# ftdiy.net
KiCad netlist of a schematic drawn in EAGLE
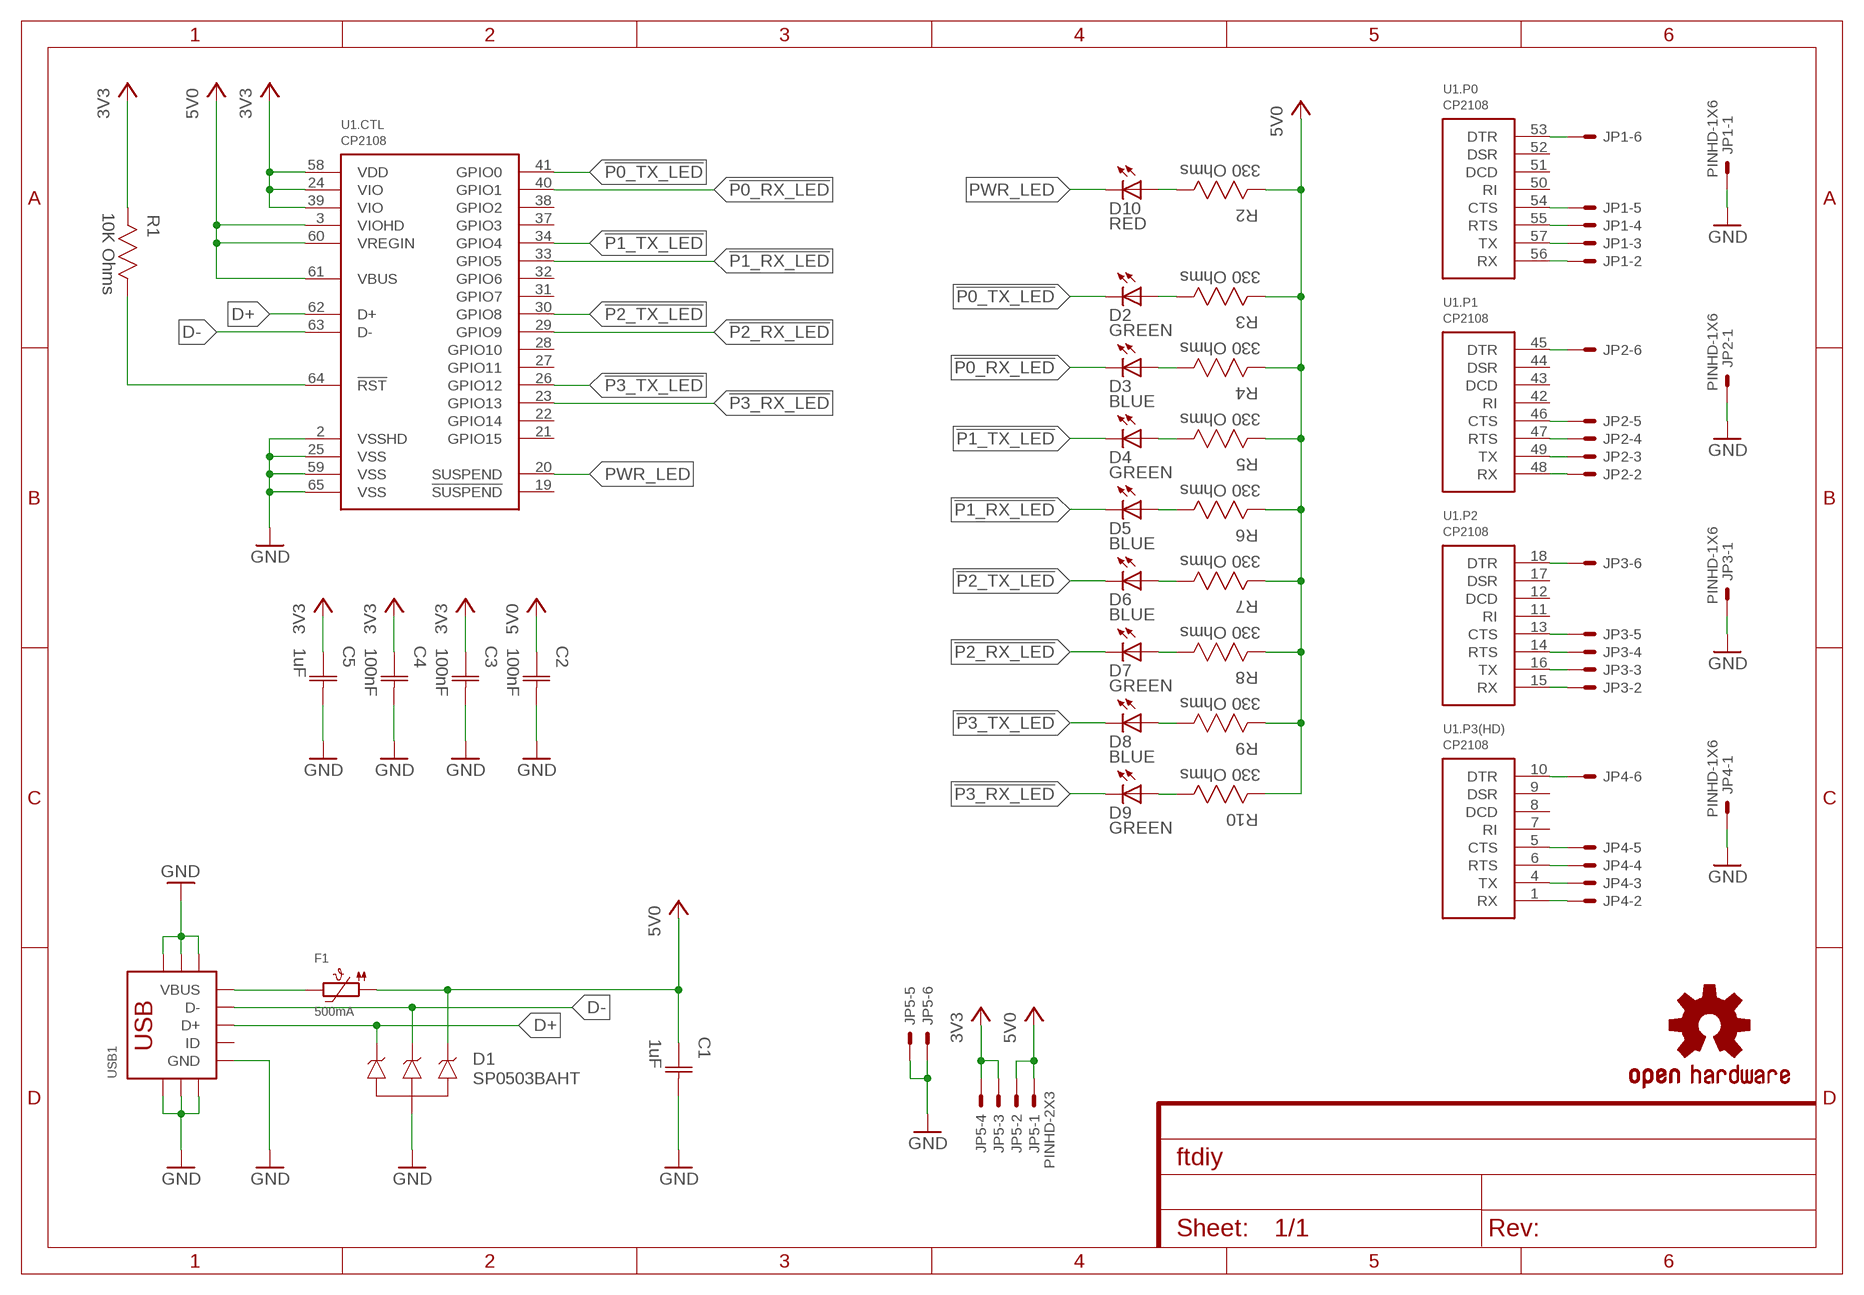
[diagram p0: schematic, sheet 1]

(export (version "E")
  (design (tool "Eeschema 10.0.6"))
  (components
    (comp (ref "C1")
      (value "1uF")
      (footprint "eagle-import:CAP0603")
      (libsource (lib "eagle-import") (part "CAPACITOR-0603"))
    )
    (comp (ref "C2")
      (value "100nF")
      (footprint "eagle-import:CAP0603")
      (libsource (lib "eagle-import") (part "CAPACITOR-0603"))
    )
    (comp (ref "C3")
      (value "100nF")
      (footprint "eagle-import:CAP0603")
      (libsource (lib "eagle-import") (part "CAPACITOR-0603"))
    )
    (comp (ref "C4")
      (value "100nF")
      (footprint "eagle-import:CAP0603")
      (libsource (lib "eagle-import") (part "CAPACITOR-0603"))
    )
    (comp (ref "C5")
      (value "1uF")
      (footprint "eagle-import:CAP0603")
      (libsource (lib "eagle-import") (part "CAPACITOR-0603"))
    )
    (comp (ref "D1")
      (value "SP0503BAHT")
      (footprint "eagle-import:SOT143")
      (libsource (lib "eagle-import") (part "SP0503BAHT"))
    )
    (comp (ref "D2")
      (value "GREEN")
      (footprint "eagle-import:0603")
      (libsource (lib "eagle-import") (part "LED0603"))
    )
    (comp (ref "D3")
      (value "BLUE")
      (footprint "eagle-import:0603")
      (libsource (lib "eagle-import") (part "LED0603"))
    )
    (comp (ref "D4")
      (value "GREEN")
      (footprint "eagle-import:0603")
      (libsource (lib "eagle-import") (part "LED0603"))
    )
    (comp (ref "D5")
      (value "BLUE")
      (footprint "eagle-import:0603")
      (libsource (lib "eagle-import") (part "LED0603"))
    )
    (comp (ref "D6")
      (value "BLUE")
      (footprint "eagle-import:0603")
      (libsource (lib "eagle-import") (part "LED0603"))
    )
    (comp (ref "D7")
      (value "GREEN")
      (footprint "eagle-import:0603")
      (libsource (lib "eagle-import") (part "LED0603"))
    )
    (comp (ref "D8")
      (value "BLUE")
      (footprint "eagle-import:0603")
      (libsource (lib "eagle-import") (part "LED0603"))
    )
    (comp (ref "D9")
      (value "GREEN")
      (footprint "eagle-import:0603")
      (libsource (lib "eagle-import") (part "LED0603"))
    )
    (comp (ref "D10")
      (value "RED")
      (footprint "eagle-import:0603")
      (libsource (lib "eagle-import") (part "LED0603"))
    )
    (comp (ref "F1")
      (value "500mA")
      (footprint "eagle-import:1206")
      (libsource (lib "eagle-import") (part "PTC1206"))
    )
    (comp (ref "JP1")
      (value "PINHD-1X6")
      (footprint "eagle-import:1X06")
      (libsource (lib "eagle-import") (part "PINHD-1X6"))
    )
    (comp (ref "JP2")
      (value "PINHD-1X6")
      (footprint "eagle-import:1X06")
      (libsource (lib "eagle-import") (part "PINHD-1X6"))
    )
    (comp (ref "JP3")
      (value "PINHD-1X6")
      (footprint "eagle-import:1X06")
      (libsource (lib "eagle-import") (part "PINHD-1X6"))
    )
    (comp (ref "JP4")
      (value "PINHD-1X6")
      (footprint "eagle-import:1X06")
      (libsource (lib "eagle-import") (part "PINHD-1X6"))
    )
    (comp (ref "JP5")
      (value "PINHD-2X3")
      (footprint "eagle-import:2X03")
      (libsource (lib "eagle-import") (part "PINHD-2X3"))
    )
    (comp (ref "LOGO1")
      (value "OSHW-LOGOM")
      (footprint "eagle-import:OSHW-LOGO-M")
      (libsource (lib "eagle-import") (part "OSHW-LOGOM"))
    )
    (comp (ref "R1")
      (value "10K Ohms")
      (footprint "eagle-import:RES0603")
      (libsource (lib "eagle-import") (part "RESISTOR-0603"))
    )
    (comp (ref "R2")
      (value "330 Ohms")
      (footprint "eagle-import:RES0603")
      (libsource (lib "eagle-import") (part "RESISTOR-0603"))
    )
    (comp (ref "R3")
      (value "330 Ohms")
      (footprint "eagle-import:RES0603")
      (libsource (lib "eagle-import") (part "RESISTOR-0603"))
    )
    (comp (ref "R4")
      (value "330 Ohms")
      (footprint "eagle-import:RES0603")
      (libsource (lib "eagle-import") (part "RESISTOR-0603"))
    )
    (comp (ref "R5")
      (value "330 Ohms")
      (footprint "eagle-import:RES0603")
      (libsource (lib "eagle-import") (part "RESISTOR-0603"))
    )
    (comp (ref "R6")
      (value "330 Ohms")
      (footprint "eagle-import:RES0603")
      (libsource (lib "eagle-import") (part "RESISTOR-0603"))
    )
    (comp (ref "R7")
      (value "330 Ohms")
      (footprint "eagle-import:RES0603")
      (libsource (lib "eagle-import") (part "RESISTOR-0603"))
    )
    (comp (ref "R8")
      (value "330 Ohms")
      (footprint "eagle-import:RES0603")
      (libsource (lib "eagle-import") (part "RESISTOR-0603"))
    )
    (comp (ref "R9")
      (value "330 Ohms")
      (footprint "eagle-import:RES0603")
      (libsource (lib "eagle-import") (part "RESISTOR-0603"))
    )
    (comp (ref "R10")
      (value "330 Ohms")
      (footprint "eagle-import:RES0603")
      (libsource (lib "eagle-import") (part "RESISTOR-0603"))
    )
    (comp (ref "U1")
      (value "CP2108")
      (footprint "eagle-import:QFN64")
      (libsource (lib "eagle-import") (part "CP2108"))
    )
    (comp (ref "USB1")
      (value "USB-MICRO-B-SMD-FLAT-SIDE")
      (footprint "eagle-import:USB-MICRO-B-SMD-FLAT-SIDE")
      (libsource (lib "eagle-import") (part "USB-MICRO-B-SMD-FLAT-SIDE"))
    )
  )
  (nets
    (net (code "1") (name "/~{P0_RX_LED}") (class "Default")
      (node (ref "D3") (pin "1") (pinfunction "C_1") (pintype "passive"))
      (node (ref "U1") (pin "40") (pinfunction "GPIO1_40") (pintype "bidirectional"))
    )
    (net (code "2") (name "/~{P0_TX_LED}") (class "Default")
      (node (ref "D2") (pin "1") (pinfunction "C_1") (pintype "passive"))
      (node (ref "U1") (pin "41") (pinfunction "GPIO0_41") (pintype "bidirectional"))
    )
    (net (code "3") (name "/~{P1_RX_LED}") (class "Default")
      (node (ref "D5") (pin "1") (pinfunction "C_1") (pintype "passive"))
      (node (ref "U1") (pin "33") (pinfunction "GPIO5_33") (pintype "bidirectional"))
    )
    (net (code "4") (name "/~{P1_TX_LED}") (class "Default")
      (node (ref "D4") (pin "1") (pinfunction "C_1") (pintype "passive"))
      (node (ref "U1") (pin "34") (pinfunction "GPIO4_34") (pintype "bidirectional"))
    )
    (net (code "5") (name "/~{P2_RX_LED}") (class "Default")
      (node (ref "D7") (pin "1") (pinfunction "C_1") (pintype "passive"))
      (node (ref "U1") (pin "29") (pinfunction "GPIO9_29") (pintype "bidirectional"))
    )
    (net (code "6") (name "/~{P2_TX_LED}") (class "Default")
      (node (ref "D6") (pin "1") (pinfunction "C_1") (pintype "passive"))
      (node (ref "U1") (pin "30") (pinfunction "GPIO8_30") (pintype "bidirectional"))
    )
    (net (code "7") (name "/~{P3_RX_LED}") (class "Default")
      (node (ref "D9") (pin "1") (pinfunction "C_1") (pintype "passive"))
      (node (ref "U1") (pin "23") (pinfunction "GPIO13_23") (pintype "bidirectional"))
    )
    (net (code "8") (name "/~{P3_TX_LED}") (class "Default")
      (node (ref "D8") (pin "1") (pinfunction "C_1") (pintype "passive"))
      (node (ref "U1") (pin "26") (pinfunction "GPIO12_26") (pintype "bidirectional"))
    )
    (net (code "9") (name "3V3") (class "Default")
      (node (ref "C3") (pin "1") (pinfunction "C1_1") (pintype "passive"))
      (node (ref "C4") (pin "1") (pinfunction "C1_1") (pintype "passive"))
      (node (ref "C5") (pin "1") (pinfunction "C1_1") (pintype "passive"))
      (node (ref "JP5") (pin "3") (pinfunction "S_3") (pintype "passive"))
      (node (ref "JP5") (pin "4") (pinfunction "S_4") (pintype "passive"))
      (node (ref "R1") (pin "2") (pinfunction "2_2") (pintype "passive"))
      (node (ref "U1") (pin "24") (pinfunction "VIO_24") (pintype "bidirectional"))
      (node (ref "U1") (pin "39") (pinfunction "VIO_39") (pintype "bidirectional"))
      (node (ref "U1") (pin "58") (pinfunction "VDD_58") (pintype "bidirectional"))
    )
    (net (code "10") (name "5V0") (class "Default")
      (node (ref "C1") (pin "1") (pinfunction "C1_1") (pintype "passive"))
      (node (ref "C2") (pin "1") (pinfunction "C1_1") (pintype "passive"))
      (node (ref "D1") (pin "4") (pinfunction "4_4") (pintype "bidirectional"))
      (node (ref "F1") (pin "1") (pinfunction "1_1") (pintype "passive"))
      (node (ref "JP5") (pin "1") (pinfunction "S_1") (pintype "passive"))
      (node (ref "JP5") (pin "2") (pinfunction "S_2") (pintype "passive"))
      (node (ref "R10") (pin "2") (pinfunction "2_2") (pintype "passive"))
      (node (ref "R2") (pin "2") (pinfunction "2_2") (pintype "passive"))
      (node (ref "R3") (pin "2") (pinfunction "2_2") (pintype "passive"))
      (node (ref "R4") (pin "2") (pinfunction "2_2") (pintype "passive"))
      (node (ref "R5") (pin "2") (pinfunction "2_2") (pintype "passive"))
      (node (ref "R6") (pin "2") (pinfunction "2_2") (pintype "passive"))
      (node (ref "R7") (pin "2") (pinfunction "2_2") (pintype "passive"))
      (node (ref "R8") (pin "2") (pinfunction "2_2") (pintype "passive"))
      (node (ref "R9") (pin "2") (pinfunction "2_2") (pintype "passive"))
      (node (ref "U1") (pin "3") (pinfunction "VIOHD_3") (pintype "bidirectional"))
      (node (ref "U1") (pin "60") (pinfunction "VREGIN_60") (pintype "bidirectional"))
      (node (ref "U1") (pin "61") (pinfunction "VBUS_61") (pintype "bidirectional"))
    )
    (net (code "11") (name "D+") (class "Default")
      (node (ref "D1") (pin "2") (pinfunction "2_2") (pintype "bidirectional"))
      (node (ref "U1") (pin "62") (pinfunction "D+_62") (pintype "bidirectional"))
      (node (ref "USB1") (pin "D+") (pinfunction "D+_D+") (pintype "bidirectional"))
    )
    (net (code "12") (name "D-") (class "Default")
      (node (ref "D1") (pin "3") (pinfunction "3_3") (pintype "bidirectional"))
      (node (ref "U1") (pin "63") (pinfunction "D-_63") (pintype "bidirectional"))
      (node (ref "USB1") (pin "D-") (pinfunction "D-_D-") (pintype "bidirectional"))
    )
    (net (code "13") (name "GND") (class "Default")
      (node (ref "C1") (pin "2") (pinfunction "C2_2") (pintype "passive"))
      (node (ref "C2") (pin "2") (pinfunction "C2_2") (pintype "passive"))
      (node (ref "C3") (pin "2") (pinfunction "C2_2") (pintype "passive"))
      (node (ref "C4") (pin "2") (pinfunction "C2_2") (pintype "passive"))
      (node (ref "C5") (pin "2") (pinfunction "C2_2") (pintype "passive"))
      (node (ref "D1") (pin "1") (pinfunction "1_1") (pintype "bidirectional"))
      (node (ref "JP1") (pin "1") (pinfunction "S_1") (pintype "passive"))
      (node (ref "JP2") (pin "1") (pinfunction "S_1") (pintype "passive"))
      (node (ref "JP3") (pin "1") (pinfunction "S_1") (pintype "passive"))
      (node (ref "JP4") (pin "1") (pinfunction "S_1") (pintype "passive"))
      (node (ref "JP5") (pin "5") (pinfunction "S_5") (pintype "passive"))
      (node (ref "JP5") (pin "6") (pinfunction "S_6") (pintype "passive"))
      (node (ref "U1") (pin "2") (pinfunction "VSSHD_2") (pintype "bidirectional"))
      (node (ref "U1") (pin "25") (pinfunction "VSS_25") (pintype "bidirectional"))
      (node (ref "U1") (pin "59") (pinfunction "VSS_59") (pintype "bidirectional"))
      (node (ref "U1") (pin "65") (pinfunction "VSS_65") (pintype "bidirectional"))
      (node (ref "USB1") (pin "GND") (pinfunction "GND_GND") (pintype "bidirectional"))
      (node (ref "USB1") (pin "SHIELD1") (pinfunction "SHIELD_SHIELD1") (pintype "bidirectional"))
      (node (ref "USB1") (pin "SHIELD2") (pinfunction "SHIELD_SHIELD2") (pintype "bidirectional"))
      (node (ref "USB1") (pin "SHIELD3") (pinfunction "SHIELD_SHIELD3") (pintype "bidirectional"))
      (node (ref "USB1") (pin "SHIELD4") (pinfunction "SHIELD_SHIELD4") (pintype "bidirectional"))
      (node (ref "USB1") (pin "SHIELD5") (pinfunction "SHIELD_SHIELD5") (pintype "bidirectional"))
      (node (ref "USB1") (pin "SHIELD6") (pinfunction "SHIELD_SHIELD6") (pintype "bidirectional"))
    )
    (net (code "14") (name "Net-(D2-A)") (class "Default")
      (node (ref "D2") (pin "2") (pinfunction "A_2") (pintype "passive"))
      (node (ref "R3") (pin "1") (pinfunction "1_1") (pintype "passive"))
    )
    (net (code "15") (name "Net-(D3-A)") (class "Default")
      (node (ref "D3") (pin "2") (pinfunction "A_2") (pintype "passive"))
      (node (ref "R4") (pin "1") (pinfunction "1_1") (pintype "passive"))
    )
    (net (code "16") (name "Net-(D4-A)") (class "Default")
      (node (ref "D4") (pin "2") (pinfunction "A_2") (pintype "passive"))
      (node (ref "R5") (pin "1") (pinfunction "1_1") (pintype "passive"))
    )
    (net (code "17") (name "Net-(D5-A)") (class "Default")
      (node (ref "D5") (pin "2") (pinfunction "A_2") (pintype "passive"))
      (node (ref "R6") (pin "1") (pinfunction "1_1") (pintype "passive"))
    )
    (net (code "18") (name "Net-(D6-A)") (class "Default")
      (node (ref "D6") (pin "2") (pinfunction "A_2") (pintype "passive"))
      (node (ref "R7") (pin "1") (pinfunction "1_1") (pintype "passive"))
    )
    (net (code "19") (name "Net-(D7-A)") (class "Default")
      (node (ref "D7") (pin "2") (pinfunction "A_2") (pintype "passive"))
      (node (ref "R8") (pin "1") (pinfunction "1_1") (pintype "passive"))
    )
    (net (code "20") (name "Net-(D8-A)") (class "Default")
      (node (ref "D8") (pin "2") (pinfunction "A_2") (pintype "passive"))
      (node (ref "R9") (pin "1") (pinfunction "1_1") (pintype "passive"))
    )
    (net (code "21") (name "Net-(D9-A)") (class "Default")
      (node (ref "D9") (pin "2") (pinfunction "A_2") (pintype "passive"))
      (node (ref "R10") (pin "1") (pinfunction "1_1") (pintype "passive"))
    )
    (net (code "22") (name "Net-(D10-A)") (class "Default")
      (node (ref "D10") (pin "2") (pinfunction "A_2") (pintype "passive"))
      (node (ref "R2") (pin "1") (pinfunction "1_1") (pintype "passive"))
    )
    (net (code "23") (name "Net-(F1-Pad2)") (class "Default")
      (node (ref "F1") (pin "2") (pinfunction "2_2") (pintype "passive"))
      (node (ref "USB1") (pin "VBUS") (pinfunction "VBUS_VBUS") (pintype "bidirectional"))
    )
    (net (code "24") (name "Net-(JP1B-S)") (class "Default")
      (node (ref "JP1") (pin "2") (pinfunction "S_2") (pintype "passive"))
      (node (ref "U1") (pin "56") (pinfunction "RX_56") (pintype "bidirectional"))
    )
    (net (code "25") (name "Net-(JP1C-S)") (class "Default")
      (node (ref "JP1") (pin "3") (pinfunction "S_3") (pintype "passive"))
      (node (ref "U1") (pin "57") (pinfunction "TX_57") (pintype "bidirectional"))
    )
    (net (code "26") (name "Net-(JP1D-S)") (class "Default")
      (node (ref "JP1") (pin "4") (pinfunction "S_4") (pintype "passive"))
      (node (ref "U1") (pin "55") (pinfunction "RTS_55") (pintype "bidirectional"))
    )
    (net (code "27") (name "Net-(JP1E-S)") (class "Default")
      (node (ref "JP1") (pin "5") (pinfunction "S_5") (pintype "passive"))
      (node (ref "U1") (pin "54") (pinfunction "CTS_54") (pintype "bidirectional"))
    )
    (net (code "28") (name "Net-(JP1F-S)") (class "Default")
      (node (ref "JP1") (pin "6") (pinfunction "S_6") (pintype "passive"))
      (node (ref "U1") (pin "53") (pinfunction "DTR_53") (pintype "bidirectional"))
    )
    (net (code "29") (name "Net-(JP2B-S)") (class "Default")
      (node (ref "JP2") (pin "2") (pinfunction "S_2") (pintype "passive"))
      (node (ref "U1") (pin "48") (pinfunction "RX_48") (pintype "bidirectional"))
    )
    (net (code "30") (name "Net-(JP2C-S)") (class "Default")
      (node (ref "JP2") (pin "3") (pinfunction "S_3") (pintype "passive"))
      (node (ref "U1") (pin "49") (pinfunction "TX_49") (pintype "bidirectional"))
    )
    (net (code "31") (name "Net-(JP2D-S)") (class "Default")
      (node (ref "JP2") (pin "4") (pinfunction "S_4") (pintype "passive"))
      (node (ref "U1") (pin "47") (pinfunction "RTS_47") (pintype "bidirectional"))
    )
    (net (code "32") (name "Net-(JP2E-S)") (class "Default")
      (node (ref "JP2") (pin "5") (pinfunction "S_5") (pintype "passive"))
      (node (ref "U1") (pin "46") (pinfunction "CTS_46") (pintype "bidirectional"))
    )
    (net (code "33") (name "Net-(JP2F-S)") (class "Default")
      (node (ref "JP2") (pin "6") (pinfunction "S_6") (pintype "passive"))
      (node (ref "U1") (pin "45") (pinfunction "DTR_45") (pintype "bidirectional"))
    )
    (net (code "34") (name "Net-(JP3B-S)") (class "Default")
      (node (ref "JP3") (pin "2") (pinfunction "S_2") (pintype "passive"))
      (node (ref "U1") (pin "15") (pinfunction "RX_15") (pintype "bidirectional"))
    )
    (net (code "35") (name "Net-(JP3C-S)") (class "Default")
      (node (ref "JP3") (pin "3") (pinfunction "S_3") (pintype "passive"))
      (node (ref "U1") (pin "16") (pinfunction "TX_16") (pintype "bidirectional"))
    )
    (net (code "36") (name "Net-(JP3D-S)") (class "Default")
      (node (ref "JP3") (pin "4") (pinfunction "S_4") (pintype "passive"))
      (node (ref "U1") (pin "14") (pinfunction "RTS_14") (pintype "bidirectional"))
    )
    (net (code "37") (name "Net-(JP3E-S)") (class "Default")
      (node (ref "JP3") (pin "5") (pinfunction "S_5") (pintype "passive"))
      (node (ref "U1") (pin "13") (pinfunction "CTS_13") (pintype "bidirectional"))
    )
    (net (code "38") (name "Net-(JP3F-S)") (class "Default")
      (node (ref "JP3") (pin "6") (pinfunction "S_6") (pintype "passive"))
      (node (ref "U1") (pin "18") (pinfunction "DTR_18") (pintype "bidirectional"))
    )
    (net (code "39") (name "Net-(JP4B-S)") (class "Default")
      (node (ref "JP4") (pin "2") (pinfunction "S_2") (pintype "passive"))
      (node (ref "U1") (pin "1") (pinfunction "RX_1") (pintype "bidirectional"))
    )
    (net (code "40") (name "Net-(JP4C-S)") (class "Default")
      (node (ref "JP4") (pin "3") (pinfunction "S_3") (pintype "passive"))
      (node (ref "U1") (pin "4") (pinfunction "TX_4") (pintype "bidirectional"))
    )
    (net (code "41") (name "Net-(JP4D-S)") (class "Default")
      (node (ref "JP4") (pin "4") (pinfunction "S_4") (pintype "passive"))
      (node (ref "U1") (pin "6") (pinfunction "RTS_6") (pintype "bidirectional"))
    )
    (net (code "42") (name "Net-(JP4E-S)") (class "Default")
      (node (ref "JP4") (pin "5") (pinfunction "S_5") (pintype "passive"))
      (node (ref "U1") (pin "5") (pinfunction "CTS_5") (pintype "bidirectional"))
    )
    (net (code "43") (name "Net-(JP4F-S)") (class "Default")
      (node (ref "JP4") (pin "6") (pinfunction "S_6") (pintype "passive"))
      (node (ref "U1") (pin "10") (pinfunction "DTR_10") (pintype "bidirectional"))
    )
    (net (code "44") (name "Net-(U1A-~{RST})") (class "Default")
      (node (ref "R1") (pin "1") (pinfunction "1_1") (pintype "passive"))
      (node (ref "U1") (pin "64") (pinfunction "~{RST}_64") (pintype "bidirectional"))
    )
    (net (code "45") (name "PWR_LED") (class "Default")
      (node (ref "D10") (pin "1") (pinfunction "C_1") (pintype "passive"))
      (node (ref "U1") (pin "20") (pinfunction "SUSPEND_20") (pintype "bidirectional"))
    )
    (net (code "46") (name "unconnected-(U1A-GPIO2-Pad38)") (class "Default")
      (node (ref "U1") (pin "38") (pinfunction "GPIO2_38") (pintype "bidirectional"))
    )
    (net (code "47") (name "unconnected-(U1A-GPIO3-Pad37)") (class "Default")
      (node (ref "U1") (pin "37") (pinfunction "GPIO3_37") (pintype "bidirectional"))
    )
    (net (code "48") (name "unconnected-(U1A-GPIO6-Pad32)") (class "Default")
      (node (ref "U1") (pin "32") (pinfunction "GPIO6_32") (pintype "bidirectional"))
    )
    (net (code "49") (name "unconnected-(U1A-GPIO7-Pad31)") (class "Default")
      (node (ref "U1") (pin "31") (pinfunction "GPIO7_31") (pintype "bidirectional"))
    )
    (net (code "50") (name "unconnected-(U1A-GPIO10-Pad28)") (class "Default")
      (node (ref "U1") (pin "28") (pinfunction "GPIO10_28") (pintype "bidirectional"))
    )
    (net (code "51") (name "unconnected-(U1A-GPIO11-Pad27)") (class "Default")
      (node (ref "U1") (pin "27") (pinfunction "GPIO11_27") (pintype "bidirectional"))
    )
    (net (code "52") (name "unconnected-(U1A-GPIO14-Pad22)") (class "Default")
      (node (ref "U1") (pin "22") (pinfunction "GPIO14_22") (pintype "bidirectional"))
    )
    (net (code "53") (name "unconnected-(U1A-GPIO15-Pad21)") (class "Default")
      (node (ref "U1") (pin "21") (pinfunction "GPIO15_21") (pintype "bidirectional"))
    )
    (net (code "54") (name "unconnected-(U1A-~{SUSPEND}-Pad19)") (class "Default")
      (node (ref "U1") (pin "19") (pinfunction "~{SUSPEND}_19") (pintype "bidirectional"))
    )
    (net (code "55") (name "unconnected-(U1B-DCD-Pad51)") (class "Default")
      (node (ref "U1") (pin "51") (pinfunction "DCD_51") (pintype "bidirectional"))
    )
    (net (code "56") (name "unconnected-(U1B-DSR-Pad52)") (class "Default")
      (node (ref "U1") (pin "52") (pinfunction "DSR_52") (pintype "bidirectional"))
    )
    (net (code "57") (name "unconnected-(U1B-RI-Pad50)") (class "Default")
      (node (ref "U1") (pin "50") (pinfunction "RI_50") (pintype "bidirectional"))
    )
    (net (code "58") (name "unconnected-(U1C-DCD-Pad43)") (class "Default")
      (node (ref "U1") (pin "43") (pinfunction "DCD_43") (pintype "bidirectional"))
    )
    (net (code "59") (name "unconnected-(U1C-DSR-Pad44)") (class "Default")
      (node (ref "U1") (pin "44") (pinfunction "DSR_44") (pintype "bidirectional"))
    )
    (net (code "60") (name "unconnected-(U1C-RI-Pad42)") (class "Default")
      (node (ref "U1") (pin "42") (pinfunction "RI_42") (pintype "bidirectional"))
    )
    (net (code "61") (name "unconnected-(U1D-DCD-Pad12)") (class "Default")
      (node (ref "U1") (pin "12") (pinfunction "DCD_12") (pintype "bidirectional"))
    )
    (net (code "62") (name "unconnected-(U1D-DSR-Pad17)") (class "Default")
      (node (ref "U1") (pin "17") (pinfunction "DSR_17") (pintype "bidirectional"))
    )
    (net (code "63") (name "unconnected-(U1D-RI-Pad11)") (class "Default")
      (node (ref "U1") (pin "11") (pinfunction "RI_11") (pintype "bidirectional"))
    )
    (net (code "64") (name "unconnected-(U1E-DCD-Pad8)") (class "Default")
      (node (ref "U1") (pin "8") (pinfunction "DCD_8") (pintype "bidirectional"))
    )
    (net (code "65") (name "unconnected-(U1E-DSR-Pad9)") (class "Default")
      (node (ref "U1") (pin "9") (pinfunction "DSR_9") (pintype "bidirectional"))
    )
    (net (code "66") (name "unconnected-(U1E-RI-Pad7)") (class "Default")
      (node (ref "U1") (pin "7") (pinfunction "RI_7") (pintype "bidirectional"))
    )
    (net (code "67") (name "unconnected-(USB1-PadID)") (class "Default")
      (node (ref "USB1") (pin "ID") (pinfunction "ID_ID") (pintype "bidirectional"))
    )
  )
)
